# BBB_Connection.net
KiCad netlist of a schematic drawn in Altium Designer
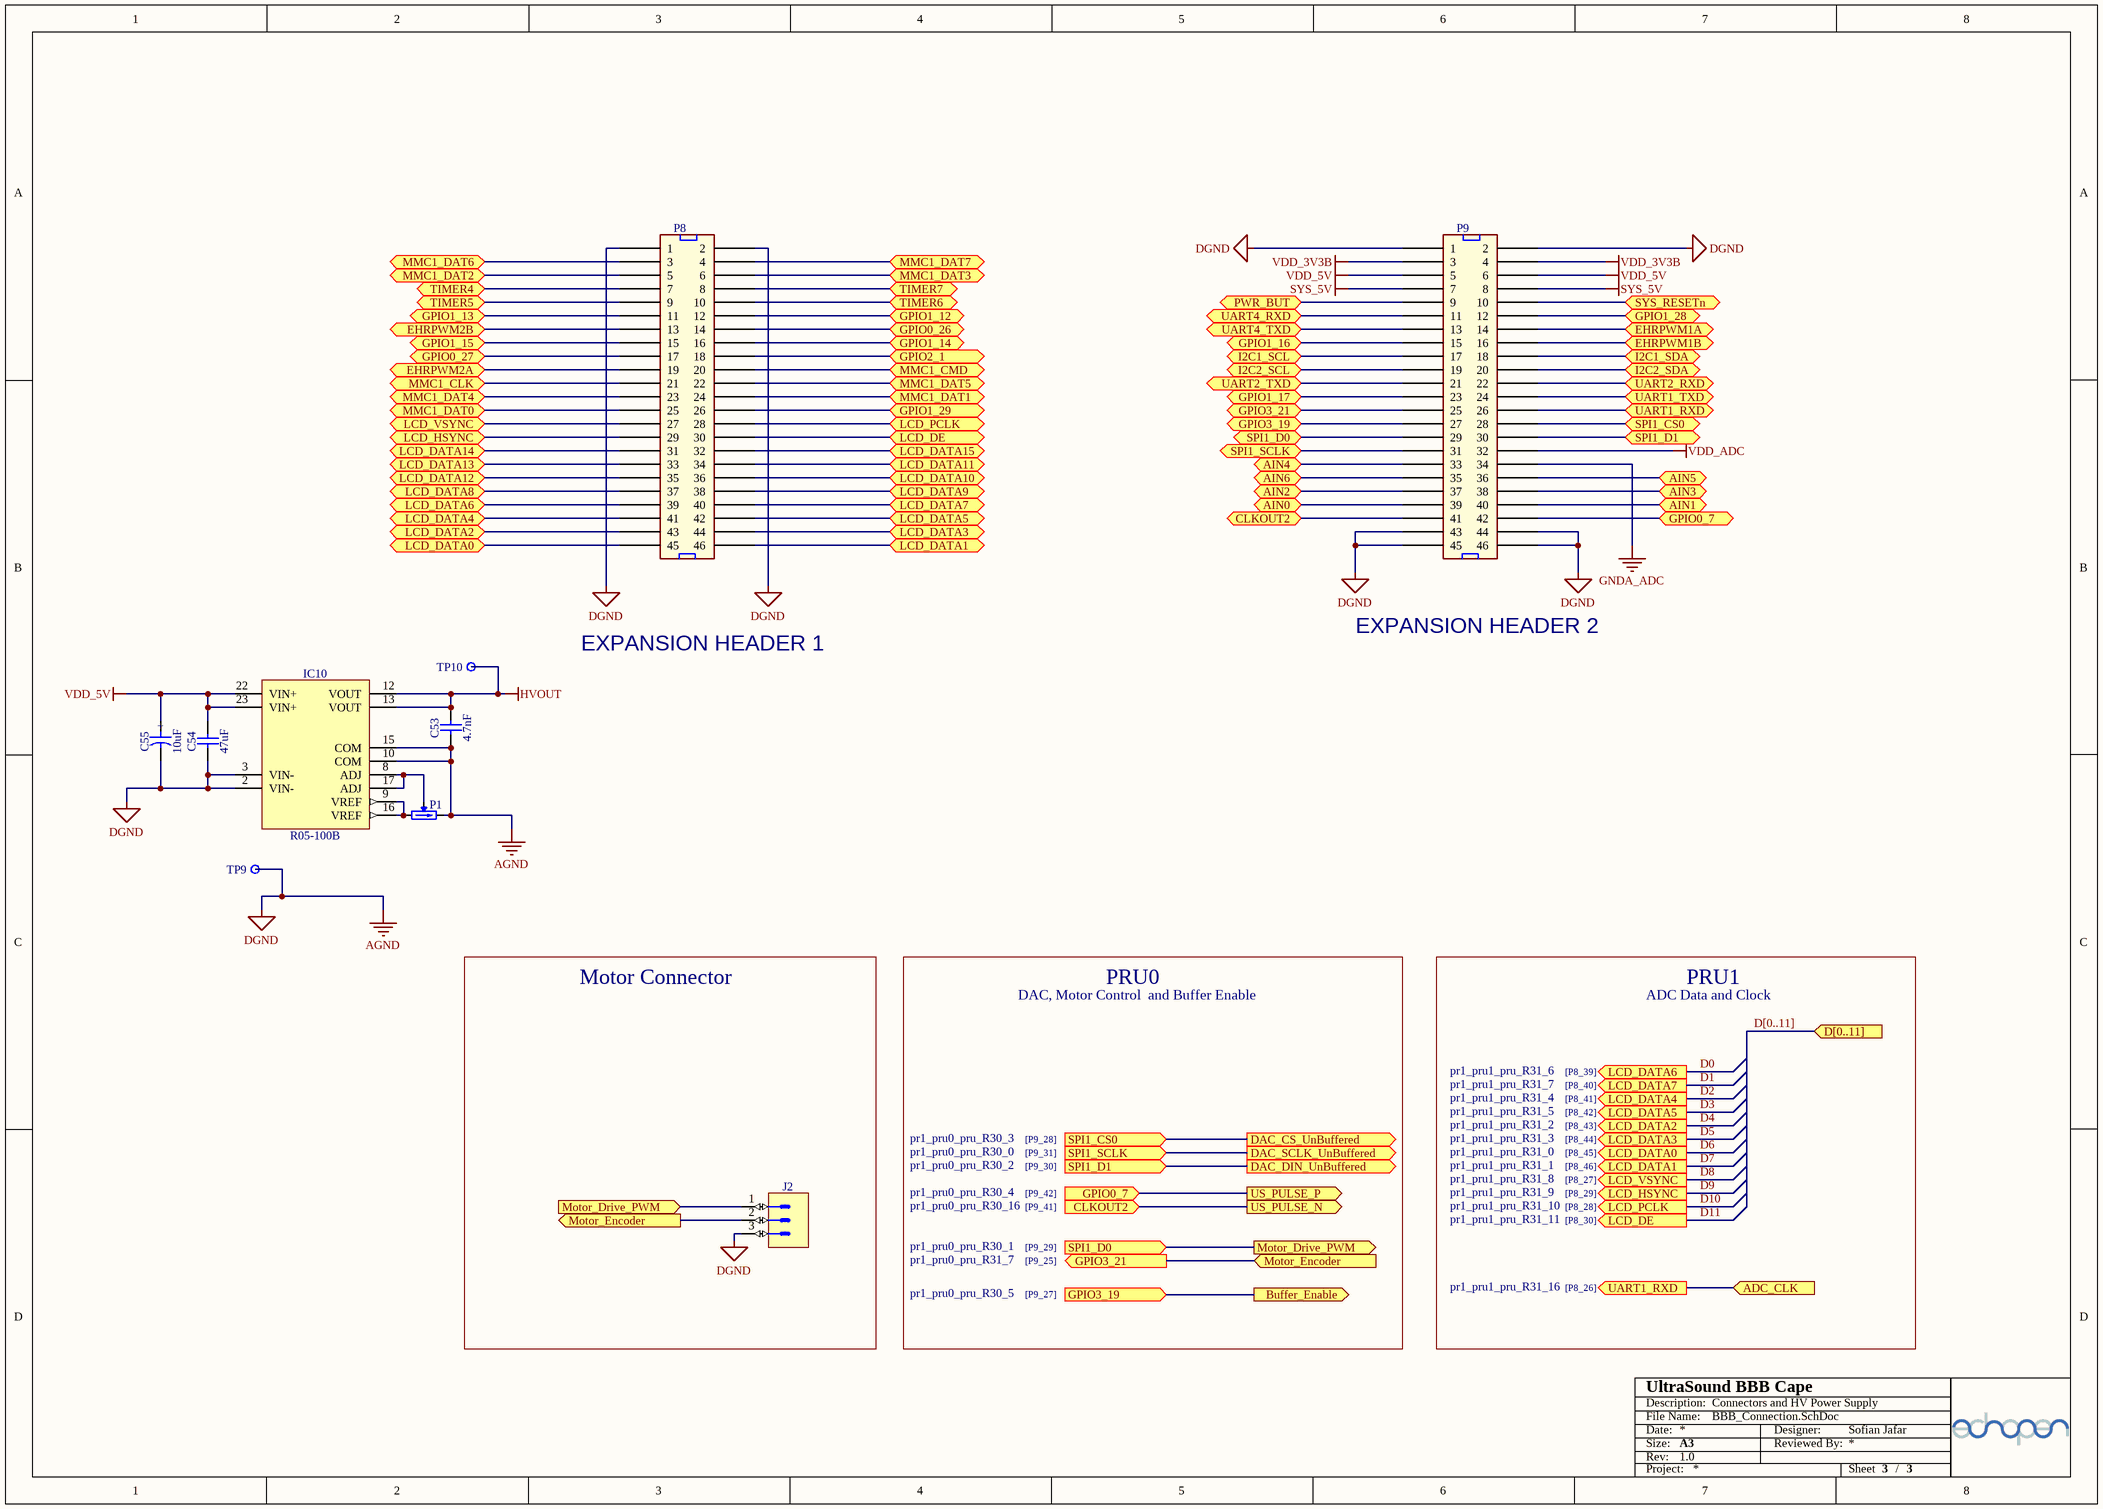
[diagram p0: BBB_Connection.SchDoc]

(export (version "E")
  (design (tool "Eeschema 10.0.6"))
  (components
    (comp (ref "C53")
      (value "4.7nF")
      (footprint "CAPC2012X110N")
      (description "Non-polarised capacitor")
      (fields
        (field (name "PART NUMBER") "CC0805_4.7NF_250V_10%_X7R")
        (field (name "VOLTAGE") "250V")
        (field (name "AUTHOR") "S. Jafar")
      )
      (libsource (lib "Sof-Capacitors") (part "Capacitor - non polarized"))
    )
    (comp (ref "C54")
      (value "47uF")
      (footprint "CAPC3216X180N")
      (description "Non-polarised capacitor")
      (fields
        (field (name "PART NUMBER") "CC1206_47UF_25V_20%_X5R")
        (field (name "VOLTAGE") "25V")
        (field (name "AUTHOR") "CERN DEM JLC")
      )
      (libsource (lib "Sof-Capacitors") (part "Capacitor - non polarized"))
    )
    (comp (ref "C55")
      (value "10uF")
      (footprint "CAPMP3528X210N")
      (description "Polarised capacitor")
      (fields
        (field (name "PART NUMBER") "CTE3528-21_10UF_16V_10%_LESR0800")
        (field (name "VOLTAGE") "16V")
        (field (name "AUTHOR") "CERN DEM JLC")
      )
      (libsource (lib "Sof-Capacitors") (part "Capacitor - polarized"))
    )
    (comp (ref "IC10")
      (value "R05-100B")
      (footprint "PWS_RECOM_R05-100B")
      (description "Power Supply")
      (fields (field (name "MANUFACTURER") "RECOM POWER") (field (name "AUTHOR") "S. Jafar"))
      (libsource (lib "Sof-ICs And Semiconductors") (part "PWS_RECOM_R05-100B"))
    )
    (comp (ref "J2")
      (value "~")
      (footprint "PHOENIX_1803439")
      (description "Connector 3 Male")
      (fields
        (field (name "PART NUMBER") "PHOENIX_1803439")
        (field (name "MANUFACTURER") "PHOENIX CONTACT")
        (field (name "AUTHOR") "CERN DEM JLC")
      )
      (libsource (lib "Sof-Connectors") (part "Connector 3 Male"))
    )
    (comp (ref "P1")
      (value "5k")
      (footprint "TRIM_BOURNS_3223W")
      (description "Trimming Potentiometer")
      (fields
        (field (name "PART NUMBER") "TRIM_11T_5K_BOURNS_3223W-1-502E")
        (field (name "POWER") "0.125W")
        (field (name "AUTHOR") "CERN DEM JLC")
      )
      (libsource (lib "Sof-Resistors") (part "Trimming Potentiometer"))
    )
    (comp (ref "P8")
      (value "~")
      (footprint "SAMTEC_TSW-123-07-L-D-LL")
      (description "Connector 46 Male")
      (fields
        (field (name "PART NUMBER") "SAMTEC_TSW-123-07-L-D-LL_a")
        (field (name "MANUFACTURER") "SAMTEC")
        (field (name "AUTHOR") "S. Jafar")
      )
      (libsource (lib "Sof-Connectors") (part "Connector 46 Male_a"))
    )
    (comp (ref "P9")
      (value "~")
      (footprint "SAMTEC_TSW-123-07-L-D-LL")
      (description "Connector 46 Male")
      (fields
        (field (name "PART NUMBER") "SAMTEC_TSW-123-07-L-D-LL_a")
        (field (name "MANUFACTURER") "SAMTEC")
        (field (name "AUTHOR") "S. Jafar")
      )
      (libsource (lib "Sof-Connectors") (part "Connector 46 Male_a"))
    )
    (comp (ref "TP9")
      (value "Test Point")
      (footprint "NICOMATIC_C12000B")
      (fields
        (field (name "PART NUMBER") "NICOMATIC_C12000B")
        (field (name "MANUFACTURER") "NICOMATIC")
        (field (name "MANUFACTURER PART NUMBER") "C12000B")
        (field (name "AUTHOR") "CERN DEM JLC")
      )
      (libsource (lib "Sof-Connectors") (part "Test Point"))
    )
    (comp (ref "TP10")
      (value "Test Point")
      (footprint "NICOMATIC_C12000B")
      (fields
        (field (name "PART NUMBER") "NICOMATIC_C12000B")
        (field (name "MANUFACTURER") "NICOMATIC")
        (field (name "MANUFACTURER PART NUMBER") "C12000B")
        (field (name "AUTHOR") "CERN DEM JLC")
      )
      (libsource (lib "Sof-Connectors") (part "Test Point"))
    )
  )
  (nets
    (net (code "1") (name "/ADC_CLK") (class "Default")
      (node (ref "P9") (pin "26") (pinfunction "26_26") (pintype "passive"))
    )
    (net (code "2") (name "/AIN0") (class "Default")
      (node (ref "P9") (pin "39") (pinfunction "39_39") (pintype "passive"))
    )
    (net (code "3") (name "/AIN1") (class "Default")
      (node (ref "P9") (pin "40") (pinfunction "40_40") (pintype "passive"))
    )
    (net (code "4") (name "/AIN2") (class "Default")
      (node (ref "P9") (pin "37") (pinfunction "37_37") (pintype "passive"))
    )
    (net (code "5") (name "/AIN3") (class "Default")
      (node (ref "P9") (pin "38") (pinfunction "38_38") (pintype "passive"))
    )
    (net (code "6") (name "/AIN4") (class "Default")
      (node (ref "P9") (pin "33") (pinfunction "33_33") (pintype "passive"))
    )
    (net (code "7") (name "/AIN5") (class "Default")
      (node (ref "P9") (pin "36") (pinfunction "36_36") (pintype "passive"))
    )
    (net (code "8") (name "/AIN6") (class "Default")
      (node (ref "P9") (pin "35") (pinfunction "35_35") (pintype "passive"))
    )
    (net (code "9") (name "/Buffer_Enable") (class "Default")
      (node (ref "P9") (pin "27") (pinfunction "27_27") (pintype "passive"))
    )
    (net (code "10") (name "/CLKOUT2") (class "Default")
      (node (ref "P9") (pin "41") (pinfunction "41_41") (pintype "passive"))
    )
    (net (code "11") (name "/D0") (class "Default")
      (node (ref "P8") (pin "39") (pinfunction "39_39") (pintype "passive"))
    )
    (net (code "12") (name "/D1") (class "Default")
      (node (ref "P8") (pin "40") (pinfunction "40_40") (pintype "passive"))
    )
    (net (code "13") (name "/D2") (class "Default")
      (node (ref "P8") (pin "41") (pinfunction "41_41") (pintype "passive"))
    )
    (net (code "14") (name "/D3") (class "Default")
      (node (ref "P8") (pin "42") (pinfunction "42_42") (pintype "passive"))
    )
    (net (code "15") (name "/D4") (class "Default")
      (node (ref "P8") (pin "43") (pinfunction "43_43") (pintype "passive"))
    )
    (net (code "16") (name "/D5") (class "Default")
      (node (ref "P8") (pin "44") (pinfunction "44_44") (pintype "passive"))
    )
    (net (code "17") (name "/D6") (class "Default")
      (node (ref "P8") (pin "45") (pinfunction "45_45") (pintype "passive"))
    )
    (net (code "18") (name "/D7") (class "Default")
      (node (ref "P8") (pin "46") (pinfunction "46_46") (pintype "passive"))
    )
    (net (code "19") (name "/D8") (class "Default")
      (node (ref "P8") (pin "27") (pinfunction "27_27") (pintype "passive"))
    )
    (net (code "20") (name "/D9") (class "Default")
      (node (ref "P8") (pin "29") (pinfunction "29_29") (pintype "passive"))
    )
    (net (code "21") (name "/D10") (class "Default")
      (node (ref "P8") (pin "28") (pinfunction "28_28") (pintype "passive"))
    )
    (net (code "22") (name "/D11") (class "Default")
      (node (ref "P8") (pin "30") (pinfunction "30_30") (pintype "passive"))
    )
    (net (code "23") (name "/DAC_CS_UnBuffered") (class "Default")
      (node (ref "P9") (pin "28") (pinfunction "28_28") (pintype "passive"))
    )
    (net (code "24") (name "/DAC_DIN_UnBuffered") (class "Default")
      (node (ref "P9") (pin "30") (pinfunction "30_30") (pintype "passive"))
    )
    (net (code "25") (name "/DAC_SCLK_UnBuffered") (class "Default")
      (node (ref "P9") (pin "31") (pinfunction "31_31") (pintype "passive"))
    )
    (net (code "27") (name "/EHRPWM1A") (class "Default")
      (node (ref "P9") (pin "14") (pinfunction "14_14") (pintype "passive"))
    )
    (net (code "28") (name "/EHRPWM1B") (class "Default")
      (node (ref "P9") (pin "16") (pinfunction "16_16") (pintype "passive"))
    )
    (net (code "29") (name "/EHRPWM2A") (class "Default")
      (node (ref "P8") (pin "19") (pinfunction "19_19") (pintype "passive"))
    )
    (net (code "30") (name "/EHRPWM2B") (class "Default")
      (node (ref "P8") (pin "13") (pinfunction "13_13") (pintype "passive"))
    )
    (net (code "31") (name "/GPIO0_7") (class "Default")
      (node (ref "P9") (pin "42") (pinfunction "42_42") (pintype "passive"))
    )
    (net (code "32") (name "/GPIO0_26") (class "Default")
      (node (ref "P8") (pin "14") (pinfunction "14_14") (pintype "passive"))
    )
    (net (code "33") (name "/GPIO0_27") (class "Default")
      (node (ref "P8") (pin "17") (pinfunction "17_17") (pintype "passive"))
    )
    (net (code "34") (name "/GPIO1_12") (class "Default")
      (node (ref "P8") (pin "12") (pinfunction "12_12") (pintype "passive"))
    )
    (net (code "35") (name "/GPIO1_13") (class "Default")
      (node (ref "P8") (pin "11") (pinfunction "11_11") (pintype "passive"))
    )
    (net (code "36") (name "/GPIO1_14") (class "Default")
      (node (ref "P8") (pin "16") (pinfunction "16_16") (pintype "passive"))
    )
    (net (code "37") (name "/GPIO1_15") (class "Default")
      (node (ref "P8") (pin "15") (pinfunction "15_15") (pintype "passive"))
    )
    (net (code "38") (name "/GPIO1_16") (class "Default")
      (node (ref "P9") (pin "15") (pinfunction "15_15") (pintype "passive"))
    )
    (net (code "39") (name "/GPIO1_17") (class "Default")
      (node (ref "P9") (pin "23") (pinfunction "23_23") (pintype "passive"))
    )
    (net (code "40") (name "/GPIO1_28") (class "Default")
      (node (ref "P9") (pin "12") (pinfunction "12_12") (pintype "passive"))
    )
    (net (code "41") (name "/GPIO1_29") (class "Default")
      (node (ref "P8") (pin "26") (pinfunction "26_26") (pintype "passive"))
    )
    (net (code "42") (name "/GPIO2_1") (class "Default")
      (node (ref "P8") (pin "18") (pinfunction "18_18") (pintype "passive"))
    )
    (net (code "43") (name "/GPIO3_21") (class "Default")
      (node (ref "J2") (pin "2") (pinfunction "2_2") (pintype "bidirectional"))
      (node (ref "P9") (pin "25") (pinfunction "25_25") (pintype "passive"))
    )
    (net (code "44") (name "/I2C1_SCL") (class "Default")
      (node (ref "P9") (pin "17") (pinfunction "17_17") (pintype "passive"))
    )
    (net (code "45") (name "/I2C1_SDA") (class "Default")
      (node (ref "P9") (pin "18") (pinfunction "18_18") (pintype "passive"))
    )
    (net (code "46") (name "/I2C2_SCL") (class "Default")
      (node (ref "P9") (pin "19") (pinfunction "19_19") (pintype "passive"))
    )
    (net (code "47") (name "/I2C2_SDA") (class "Default")
      (node (ref "P9") (pin "20") (pinfunction "20_20") (pintype "passive"))
    )
    (net (code "48") (name "/LCD_DATA8") (class "Default")
      (node (ref "P8") (pin "37") (pinfunction "37_37") (pintype "passive"))
    )
    (net (code "49") (name "/LCD_DATA9") (class "Default")
      (node (ref "P8") (pin "38") (pinfunction "38_38") (pintype "passive"))
    )
    (net (code "50") (name "/LCD_DATA10") (class "Default")
      (node (ref "P8") (pin "36") (pinfunction "36_36") (pintype "passive"))
    )
    (net (code "51") (name "/LCD_DATA11") (class "Default")
      (node (ref "P8") (pin "34") (pinfunction "34_34") (pintype "passive"))
    )
    (net (code "52") (name "/LCD_DATA12") (class "Default")
      (node (ref "P8") (pin "35") (pinfunction "35_35") (pintype "passive"))
    )
    (net (code "53") (name "/LCD_DATA13") (class "Default")
      (node (ref "P8") (pin "33") (pinfunction "33_33") (pintype "passive"))
    )
    (net (code "54") (name "/LCD_DATA14") (class "Default")
      (node (ref "P8") (pin "31") (pinfunction "31_31") (pintype "passive"))
    )
    (net (code "55") (name "/LCD_DATA15") (class "Default")
      (node (ref "P8") (pin "32") (pinfunction "32_32") (pintype "passive"))
    )
    (net (code "56") (name "/MMC1_CLK") (class "Default")
      (node (ref "P8") (pin "21") (pinfunction "21_21") (pintype "passive"))
    )
    (net (code "57") (name "/MMC1_CMD") (class "Default")
      (node (ref "P8") (pin "20") (pinfunction "20_20") (pintype "passive"))
    )
    (net (code "58") (name "/MMC1_DAT0") (class "Default")
      (node (ref "P8") (pin "25") (pinfunction "25_25") (pintype "passive"))
    )
    (net (code "59") (name "/MMC1_DAT1") (class "Default")
      (node (ref "P8") (pin "24") (pinfunction "24_24") (pintype "passive"))
    )
    (net (code "60") (name "/MMC1_DAT2") (class "Default")
      (node (ref "P8") (pin "5") (pinfunction "5_5") (pintype "passive"))
    )
    (net (code "61") (name "/MMC1_DAT3") (class "Default")
      (node (ref "P8") (pin "6") (pinfunction "6_6") (pintype "passive"))
    )
    (net (code "62") (name "/MMC1_DAT4") (class "Default")
      (node (ref "P8") (pin "23") (pinfunction "23_23") (pintype "passive"))
    )
    (net (code "63") (name "/MMC1_DAT5") (class "Default")
      (node (ref "P8") (pin "22") (pinfunction "22_22") (pintype "passive"))
    )
    (net (code "64") (name "/MMC1_DAT6") (class "Default")
      (node (ref "P8") (pin "3") (pinfunction "3_3") (pintype "passive"))
    )
    (net (code "65") (name "/MMC1_DAT7") (class "Default")
      (node (ref "P8") (pin "4") (pinfunction "4_4") (pintype "passive"))
    )
    (net (code "66") (name "/Motor_Drive_PWM") (class "Default")
      (node (ref "J2") (pin "1") (pinfunction "1_1") (pintype "bidirectional"))
      (node (ref "P9") (pin "29") (pinfunction "29_29") (pintype "passive"))
    )
    (net (code "67") (name "/PWR_BUT") (class "Default")
      (node (ref "P9") (pin "9") (pinfunction "9_9") (pintype "passive"))
    )
    (net (code "68") (name "/SYS_RESETn") (class "Default")
      (node (ref "P9") (pin "10") (pinfunction "10_10") (pintype "passive"))
    )
    (net (code "69") (name "/TIMER4") (class "Default")
      (node (ref "P8") (pin "7") (pinfunction "7_7") (pintype "passive"))
    )
    (net (code "70") (name "/TIMER5") (class "Default")
      (node (ref "P8") (pin "9") (pinfunction "9_9") (pintype "passive"))
    )
    (net (code "71") (name "/TIMER6") (class "Default")
      (node (ref "P8") (pin "10") (pinfunction "10_10") (pintype "passive"))
    )
    (net (code "72") (name "/TIMER7") (class "Default")
      (node (ref "P8") (pin "8") (pinfunction "8_8") (pintype "passive"))
    )
    (net (code "73") (name "/UART1_TXD") (class "Default")
      (node (ref "P9") (pin "24") (pinfunction "24_24") (pintype "passive"))
    )
    (net (code "74") (name "/UART2_RXD") (class "Default")
      (node (ref "P9") (pin "22") (pinfunction "22_22") (pintype "passive"))
    )
    (net (code "75") (name "/UART2_TXD") (class "Default")
      (node (ref "P9") (pin "21") (pinfunction "21_21") (pintype "passive"))
    )
    (net (code "76") (name "/UART4_RXD") (class "Default")
      (node (ref "P9") (pin "11") (pinfunction "11_11") (pintype "passive"))
    )
    (net (code "77") (name "/UART4_TXD") (class "Default")
      (node (ref "P9") (pin "13") (pinfunction "13_13") (pintype "passive"))
    )
    (net (code "78") (name "AGND") (class "Default")
      (node (ref "C53") (pin "1") (pinfunction "1_1") (pintype "passive"))
      (node (ref "C54") (pin "1") (pinfunction "1_1") (pintype "passive"))
      (node (ref "C55") (pin "2") (pinfunction "2_2") (pintype "passive"))
      (node (ref "IC10") (pin "10") (pinfunction "COM_10") (pintype "power_in"))
      (node (ref "IC10") (pin "15") (pinfunction "COM_15") (pintype "power_in"))
      (node (ref "IC10") (pin "2") (pinfunction "VIN-_2") (pintype "passive"))
      (node (ref "IC10") (pin "3") (pinfunction "VIN-_3") (pintype "passive"))
      (node (ref "J2") (pin "3") (pinfunction "3_3") (pintype "bidirectional"))
      (node (ref "P1") (pin "3") (pinfunction "CW_3") (pintype "passive"))
      (node (ref "P8") (pin "1") (pinfunction "1_1") (pintype "passive"))
      (node (ref "P8") (pin "2") (pinfunction "2_2") (pintype "passive"))
      (node (ref "P9") (pin "1") (pinfunction "1_1") (pintype "passive"))
      (node (ref "P9") (pin "2") (pinfunction "2_2") (pintype "passive"))
      (node (ref "P9") (pin "43") (pinfunction "43_43") (pintype "passive"))
      (node (ref "P9") (pin "44") (pinfunction "44_44") (pintype "passive"))
      (node (ref "P9") (pin "45") (pinfunction "45_45") (pintype "passive"))
      (node (ref "P9") (pin "46") (pinfunction "46_46") (pintype "passive"))
      (node (ref "TP9") (pin "1") (pinfunction "1_1") (pintype "bidirectional"))
    )
    (net (code "79") (name "GNDA_ADC") (class "Default")
      (node (ref "P9") (pin "34") (pinfunction "34_34") (pintype "passive"))
    )
    (net (code "80") (name "HVOUT") (class "Default")
      (node (ref "C53") (pin "2") (pinfunction "2_2") (pintype "passive"))
      (node (ref "IC10") (pin "12") (pinfunction "VOUT_12") (pintype "power_in"))
      (node (ref "IC10") (pin "13") (pinfunction "VOUT_13") (pintype "power_in"))
      (node (ref "TP10") (pin "1") (pinfunction "1_1") (pintype "bidirectional"))
    )
    (net (code "81") (name "Net-(P1-CCW)") (class "Default")
      (node (ref "IC10") (pin "16") (pinfunction "VREF_16") (pintype "output"))
      (node (ref "IC10") (pin "9") (pinfunction "VREF_9") (pintype "output"))
      (node (ref "P1") (pin "1") (pinfunction "CCW_1") (pintype "passive"))
    )
    (net (code "82") (name "Net-(P1-W)") (class "Default")
      (node (ref "IC10") (pin "17") (pinfunction "ADJ_17") (pintype "passive"))
      (node (ref "IC10") (pin "8") (pinfunction "ADJ_8") (pintype "passive"))
      (node (ref "P1") (pin "2") (pinfunction "W_2") (pintype "passive"))
    )
    (net (code "83") (name "SYS_5V") (class "Default")
      (node (ref "P9") (pin "7") (pinfunction "7_7") (pintype "passive"))
      (node (ref "P9") (pin "8") (pinfunction "8_8") (pintype "passive"))
    )
    (net (code "84") (name "VDD_3V3B") (class "Default")
      (node (ref "P9") (pin "3") (pinfunction "3_3") (pintype "passive"))
      (node (ref "P9") (pin "4") (pinfunction "4_4") (pintype "passive"))
    )
    (net (code "85") (name "VDD_5V") (class "Default")
      (node (ref "C54") (pin "2") (pinfunction "2_2") (pintype "passive"))
      (node (ref "C55") (pin "1") (pinfunction "1_1") (pintype "passive"))
      (node (ref "IC10") (pin "22") (pinfunction "VIN+_22") (pintype "power_in"))
      (node (ref "IC10") (pin "23") (pinfunction "VIN+_23") (pintype "power_in"))
      (node (ref "P9") (pin "5") (pinfunction "5_5") (pintype "passive"))
      (node (ref "P9") (pin "6") (pinfunction "6_6") (pintype "passive"))
    )
    (net (code "86") (name "VDD_ADC") (class "Default")
      (node (ref "P9") (pin "32") (pinfunction "32_32") (pintype "passive"))
    )
  )
)
